# PCB_HYDRA_Sensors_V1_1.net
KiCad netlist of a schematic drawn in EAGLE
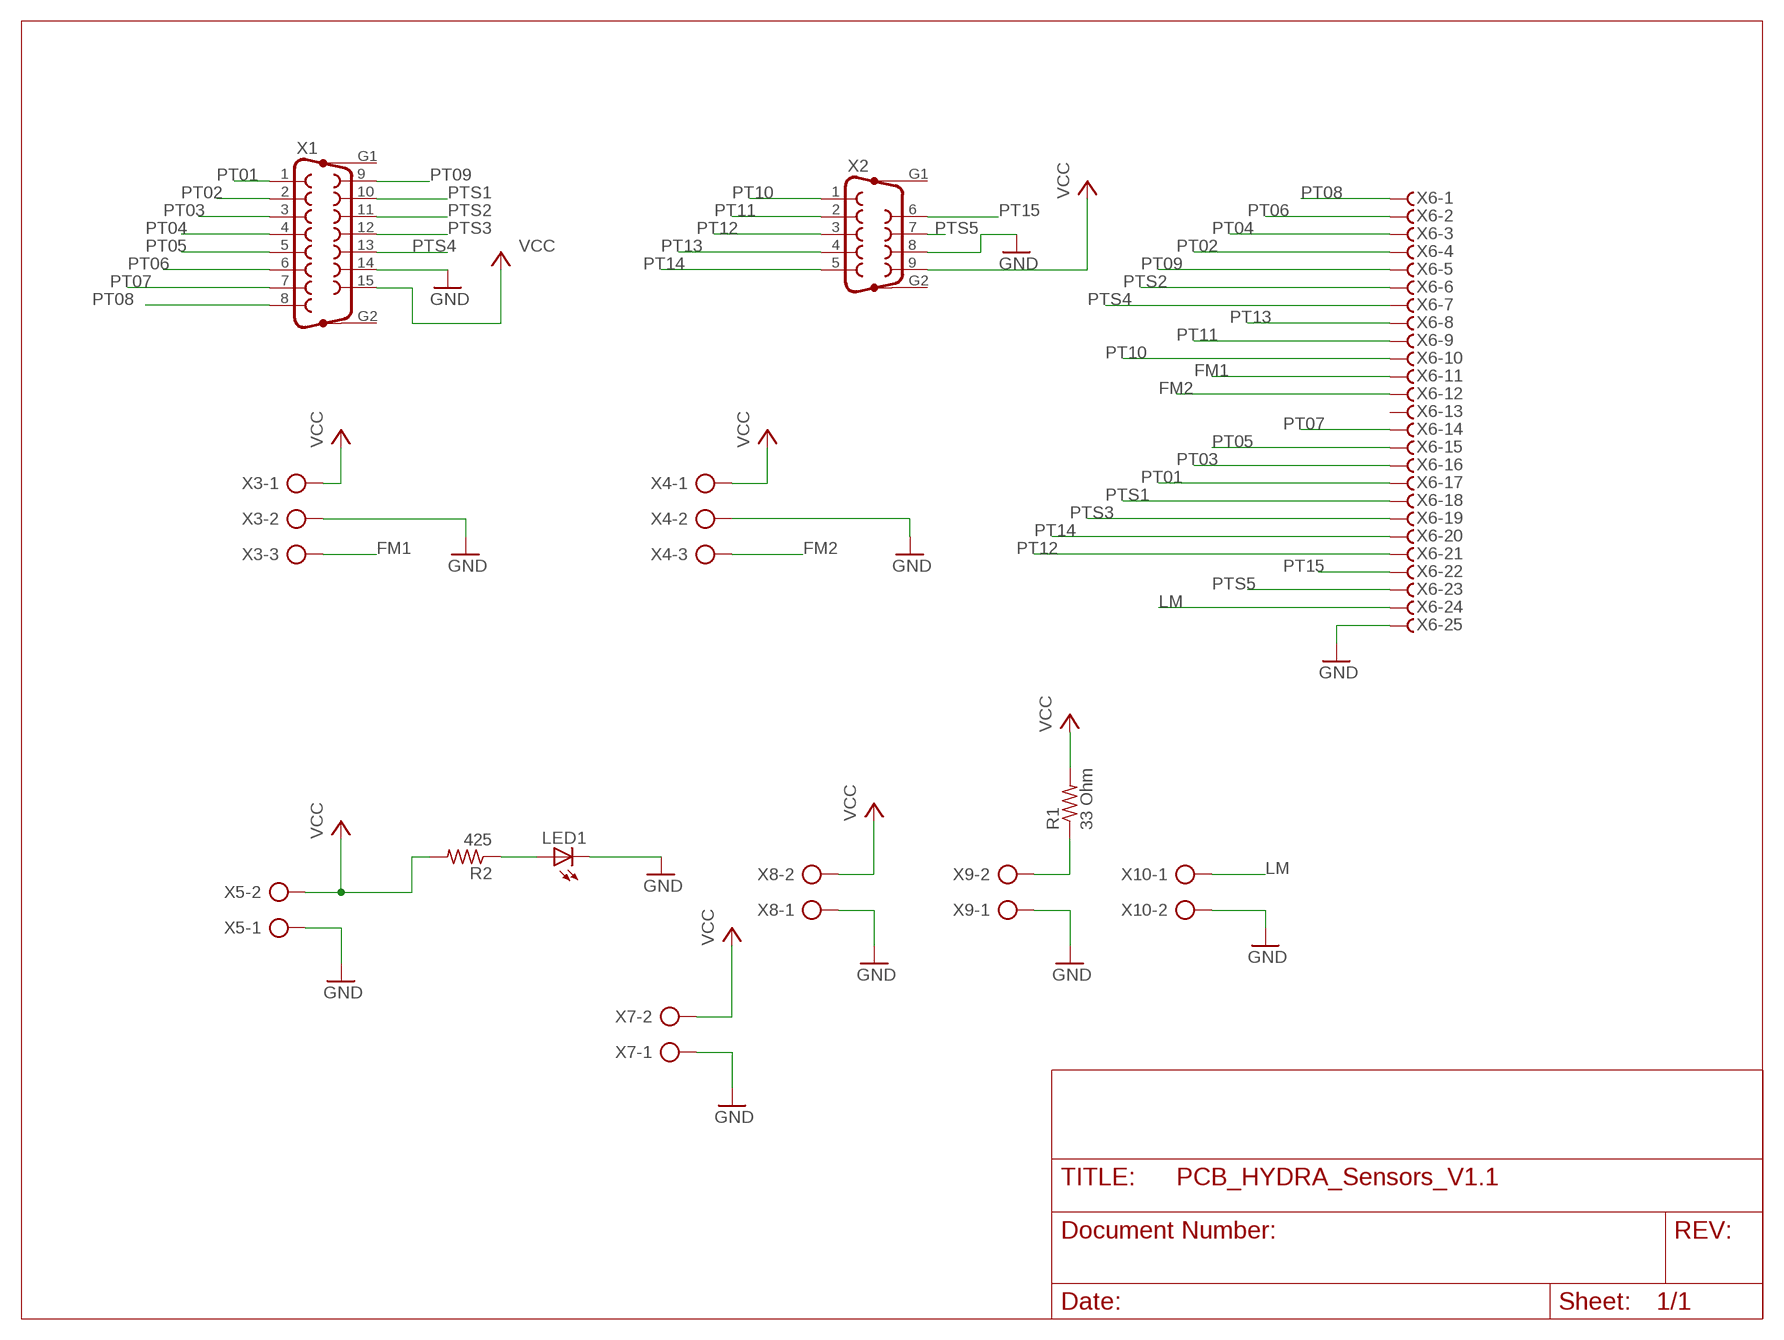
[diagram p0: schematic, sheet 1]

(export (version "E")
  (design (tool "Eeschema 10.0.6"))
  (components
    (comp (ref "LED1")
      (value "LEDCHIPLED_0805")
      (footprint "eagle-import:CHIPLED_0805")
      (libsource (lib "eagle-import") (part "LEDCHIPLED_0805"))
    )
    (comp (ref "R1")
      (value "33 Ohm")
      (footprint "eagle-import:M1206")
      (libsource (lib "eagle-import") (part "R-US_M1206"))
    )
    (comp (ref "R2")
      (value "425")
      (footprint "eagle-import:M1206")
      (fields (field (name "MPN") "M2012ES1G01"))
      (libsource (lib "eagle-import") (part "R-US_M1206"))
    )
    (comp (ref "X1")
      (value "F15HP")
      (footprint "eagle-import:F15HP")
      (libsource (lib "eagle-import") (part "F15HP"))
    )
    (comp (ref "X2")
      (value "F09HP")
      (footprint "eagle-import:F09HP")
      (libsource (lib "eagle-import") (part "F09HP"))
    )
    (comp (ref "X3")
      (value "AK300/3")
      (footprint "eagle-import:AK300_3")
      (libsource (lib "eagle-import") (part "AK300/3"))
    )
    (comp (ref "X4")
      (value "AK300/3")
      (footprint "eagle-import:AK300_3")
      (libsource (lib "eagle-import") (part "AK300/3"))
    )
    (comp (ref "X5")
      (value "AK300/2")
      (footprint "eagle-import:AK300_2")
      (libsource (lib "eagle-import") (part "AK300/2"))
    )
    (comp (ref "X6")
      (value "F25HPS")
      (footprint "eagle-import:F25HP")
      (libsource (lib "eagle-import") (part "F25?SHP"))
    )
    (comp (ref "X7")
      (value "AK300/2")
      (footprint "eagle-import:AK300_2")
      (libsource (lib "eagle-import") (part "AK300/2"))
    )
    (comp (ref "X8")
      (value "AK300/2")
      (footprint "eagle-import:AK300_2")
      (libsource (lib "eagle-import") (part "AK300/2"))
    )
    (comp (ref "X9")
      (value "AK300/2")
      (footprint "eagle-import:AK300_2")
      (libsource (lib "eagle-import") (part "AK300/2"))
    )
    (comp (ref "X10")
      (value "AK300/2")
      (footprint "eagle-import:AK300_2")
      (libsource (lib "eagle-import") (part "AK300/2"))
    )
  )
  (nets
    (net (code "1") (name "/FM1") (class "Default")
      (node (ref "X3") (pin "3") (pinfunction "KL_3") (pintype "passive"))
      (node (ref "X6") (pin "11") (pinfunction "F_11") (pintype "passive"))
    )
    (net (code "2") (name "/FM2") (class "Default")
      (node (ref "X4") (pin "3") (pinfunction "KL_3") (pintype "passive"))
      (node (ref "X6") (pin "12") (pinfunction "F_12") (pintype "passive"))
    )
    (net (code "3") (name "/LM") (class "Default")
      (node (ref "X10") (pin "1") (pinfunction "KL_1") (pintype "passive"))
      (node (ref "X6") (pin "24") (pinfunction "F_24") (pintype "passive"))
    )
    (net (code "4") (name "/PT01") (class "Default")
      (node (ref "X1") (pin "1") (pinfunction "1_1") (pintype "passive"))
      (node (ref "X6") (pin "17") (pinfunction "F_17") (pintype "passive"))
    )
    (net (code "5") (name "/PT02") (class "Default")
      (node (ref "X1") (pin "2") (pinfunction "2_2") (pintype "passive"))
      (node (ref "X6") (pin "4") (pinfunction "F_4") (pintype "passive"))
    )
    (net (code "6") (name "/PT03") (class "Default")
      (node (ref "X1") (pin "3") (pinfunction "3_3") (pintype "passive"))
      (node (ref "X6") (pin "16") (pinfunction "F_16") (pintype "passive"))
    )
    (net (code "7") (name "/PT04") (class "Default")
      (node (ref "X1") (pin "4") (pinfunction "4_4") (pintype "passive"))
      (node (ref "X6") (pin "3") (pinfunction "F_3") (pintype "passive"))
    )
    (net (code "8") (name "/PT05") (class "Default")
      (node (ref "X1") (pin "5") (pinfunction "5_5") (pintype "passive"))
      (node (ref "X6") (pin "15") (pinfunction "F_15") (pintype "passive"))
    )
    (net (code "9") (name "/PT06") (class "Default")
      (node (ref "X1") (pin "6") (pinfunction "6_6") (pintype "passive"))
      (node (ref "X6") (pin "2") (pinfunction "F_2") (pintype "passive"))
    )
    (net (code "10") (name "/PT07") (class "Default")
      (node (ref "X1") (pin "7") (pinfunction "7_7") (pintype "passive"))
      (node (ref "X6") (pin "14") (pinfunction "F_14") (pintype "passive"))
    )
    (net (code "11") (name "/PT08") (class "Default")
      (node (ref "X1") (pin "8") (pinfunction "8_8") (pintype "passive"))
      (node (ref "X6") (pin "1") (pinfunction "F_1") (pintype "passive"))
    )
    (net (code "12") (name "/PT09") (class "Default")
      (node (ref "X1") (pin "9") (pinfunction "9_9") (pintype "passive"))
      (node (ref "X6") (pin "5") (pinfunction "F_5") (pintype "passive"))
    )
    (net (code "13") (name "/PT10") (class "Default")
      (node (ref "X2") (pin "1") (pinfunction "1_1") (pintype "passive"))
      (node (ref "X6") (pin "10") (pinfunction "F_10") (pintype "passive"))
    )
    (net (code "14") (name "/PT11") (class "Default")
      (node (ref "X2") (pin "2") (pinfunction "2_2") (pintype "passive"))
      (node (ref "X6") (pin "9") (pinfunction "F_9") (pintype "passive"))
    )
    (net (code "15") (name "/PT12") (class "Default")
      (node (ref "X2") (pin "3") (pinfunction "3_3") (pintype "passive"))
      (node (ref "X6") (pin "21") (pinfunction "F_21") (pintype "passive"))
    )
    (net (code "16") (name "/PT13") (class "Default")
      (node (ref "X2") (pin "4") (pinfunction "4_4") (pintype "passive"))
      (node (ref "X6") (pin "8") (pinfunction "F_8") (pintype "passive"))
    )
    (net (code "17") (name "/PT14") (class "Default")
      (node (ref "X2") (pin "5") (pinfunction "5_5") (pintype "passive"))
      (node (ref "X6") (pin "20") (pinfunction "F_20") (pintype "passive"))
    )
    (net (code "18") (name "/PT15") (class "Default")
      (node (ref "X2") (pin "6") (pinfunction "6_6") (pintype "passive"))
      (node (ref "X6") (pin "22") (pinfunction "F_22") (pintype "passive"))
    )
    (net (code "19") (name "/PTS1") (class "Default")
      (node (ref "X1") (pin "10") (pinfunction "10_10") (pintype "passive"))
      (node (ref "X6") (pin "18") (pinfunction "F_18") (pintype "passive"))
    )
    (net (code "20") (name "/PTS2") (class "Default")
      (node (ref "X1") (pin "11") (pinfunction "11_11") (pintype "passive"))
      (node (ref "X6") (pin "6") (pinfunction "F_6") (pintype "passive"))
    )
    (net (code "21") (name "/PTS3") (class "Default")
      (node (ref "X1") (pin "12") (pinfunction "12_12") (pintype "passive"))
      (node (ref "X6") (pin "19") (pinfunction "F_19") (pintype "passive"))
    )
    (net (code "22") (name "/PTS4") (class "Default")
      (node (ref "X1") (pin "13") (pinfunction "13_13") (pintype "passive"))
      (node (ref "X6") (pin "7") (pinfunction "F_7") (pintype "passive"))
    )
    (net (code "23") (name "/PTS5") (class "Default")
      (node (ref "X2") (pin "7") (pinfunction "7_7") (pintype "passive"))
      (node (ref "X6") (pin "23") (pinfunction "F_23") (pintype "passive"))
    )
    (net (code "24") (name "GND") (class "Default")
      (node (ref "LED1") (pin "C") (pinfunction "C_C") (pintype "passive"))
      (node (ref "X1") (pin "14") (pinfunction "14_14") (pintype "passive"))
      (node (ref "X10") (pin "2") (pinfunction "KL_2") (pintype "passive"))
      (node (ref "X2") (pin "8") (pinfunction "8_8") (pintype "passive"))
      (node (ref "X3") (pin "2") (pinfunction "KL_2") (pintype "passive"))
      (node (ref "X4") (pin "2") (pinfunction "KL_2") (pintype "passive"))
      (node (ref "X5") (pin "1") (pinfunction "KL_1") (pintype "passive"))
      (node (ref "X6") (pin "25") (pinfunction "F_25") (pintype "passive"))
      (node (ref "X7") (pin "1") (pinfunction "KL_1") (pintype "passive"))
      (node (ref "X8") (pin "1") (pinfunction "KL_1") (pintype "passive"))
      (node (ref "X9") (pin "1") (pinfunction "KL_1") (pintype "passive"))
    )
    (net (code "25") (name "Net-(LED1-PadA)") (class "Default")
      (node (ref "LED1") (pin "A") (pinfunction "A_A") (pintype "passive"))
      (node (ref "R2") (pin "1") (pinfunction "1_1") (pintype "passive"))
    )
    (net (code "26") (name "Net-(X9B-KL)") (class "Default")
      (node (ref "R1") (pin "1") (pinfunction "1_1") (pintype "passive"))
      (node (ref "X9") (pin "2") (pinfunction "KL_2") (pintype "passive"))
    )
    (net (code "27") (name "VCC") (class "Default")
      (node (ref "R1") (pin "2") (pinfunction "2_2") (pintype "passive"))
      (node (ref "R2") (pin "2") (pinfunction "2_2") (pintype "passive"))
      (node (ref "X1") (pin "15") (pinfunction "15_15") (pintype "passive"))
      (node (ref "X2") (pin "9") (pinfunction "9_9") (pintype "passive"))
      (node (ref "X3") (pin "1") (pinfunction "KL_1") (pintype "passive"))
      (node (ref "X4") (pin "1") (pinfunction "KL_1") (pintype "passive"))
      (node (ref "X5") (pin "2") (pinfunction "KL_2") (pintype "passive"))
      (node (ref "X7") (pin "2") (pinfunction "KL_2") (pintype "passive"))
      (node (ref "X8") (pin "2") (pinfunction "KL_2") (pintype "passive"))
    )
    (net (code "28") (name "unconnected-(X1-PadG1)") (class "Default")
      (node (ref "X1") (pin "G1") (pinfunction "G1_G1") (pintype "passive"))
    )
    (net (code "29") (name "unconnected-(X1-PadG2)") (class "Default")
      (node (ref "X1") (pin "G2") (pinfunction "G2_G2") (pintype "passive"))
    )
    (net (code "30") (name "unconnected-(X2-PadG1)") (class "Default")
      (node (ref "X2") (pin "G1") (pinfunction "G1_G1") (pintype "passive"))
    )
    (net (code "31") (name "unconnected-(X2-PadG2)") (class "Default")
      (node (ref "X2") (pin "G2") (pinfunction "G2_G2") (pintype "passive"))
    )
    (net (code "32") (name "unconnected-(X6E-F-Pad13)") (class "Default")
      (node (ref "X6") (pin "13") (pinfunction "F_13") (pintype "passive"))
    )
  )
)
